# OpenthermGWMini.net
KiCad netlist of a schematic drawn in EAGLE
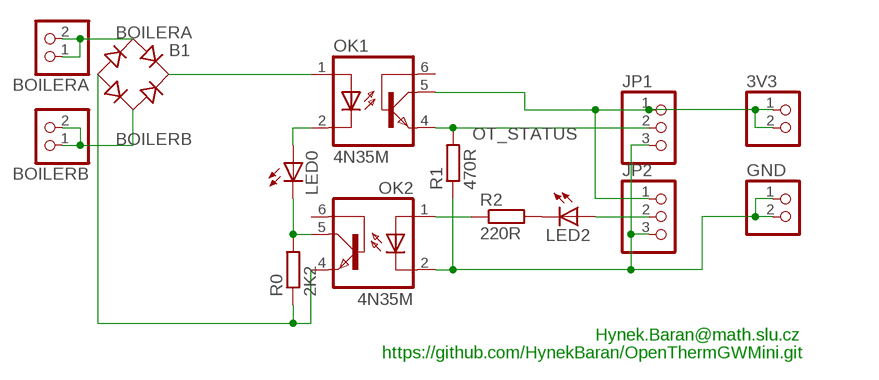
[diagram p0: schematic, sheet 1]

(export (version "E")
  (design (tool "Eeschema 10.0.6"))
  (components
    (comp (ref "3V3")
      (value "PINHD-1X2")
      (footprint "eagle-import:1X02")
      (libsource (lib "eagle-import") (part "pinheadHB_PINHD-1X2"))
    )
    (comp (ref "B1")
      (value "RB1A")
      (footprint "eagle-import:RB1A")
      (libsource (lib "eagle-import") (part "RB1A"))
    )
    (comp (ref "BOILERA")
      (value "PINHD-1X2")
      (footprint "eagle-import:1X02")
      (libsource (lib "eagle-import") (part "PINHD-1X2"))
    )
    (comp (ref "BOILERB")
      (value "PINHD-1X2")
      (footprint "eagle-import:1X02")
      (libsource (lib "eagle-import") (part "PINHD-1X2"))
    )
    (comp (ref "GND")
      (value "PINHD-1X2")
      (footprint "eagle-import:1X02")
      (libsource (lib "eagle-import") (part "pinheadHB_PINHD-1X2"))
    )
    (comp (ref "JP1")
      (value "PINHD-1X3")
      (footprint "eagle-import:1X03")
      (libsource (lib "eagle-import") (part "PINHD-1X3"))
    )
    (comp (ref "JP2")
      (value "PINHD-1X3")
      (footprint "eagle-import:1X03")
      (libsource (lib "eagle-import") (part "PINHD-1X3"))
    )
    (comp (ref "LED0")
      (value "LED3MM")
      (footprint "eagle-import:LED3MM")
      (libsource (lib "eagle-import") (part "LED3MM"))
    )
    (comp (ref "LED2")
      (value "LED3MM")
      (footprint "eagle-import:LED3MM")
      (libsource (lib "eagle-import") (part "LED3MM"))
    )
    (comp (ref "OK1")
      (value "4N35M")
      (footprint "eagle-import:DIL06")
      (fields (field (name "MPN") "4N35-M"))
      (libsource (lib "eagle-import") (part "4N?M35"))
    )
    (comp (ref "OK2")
      (value "4N35M")
      (footprint "eagle-import:DIL06")
      (fields (field (name "MPN") "4N35-M"))
      (libsource (lib "eagle-import") (part "4N?M35"))
    )
    (comp (ref "R0")
      (value "2K2")
      (footprint "eagle-import:0204_5")
      (libsource (lib "eagle-import") (part "R-EU_0204/5"))
    )
    (comp (ref "R1")
      (value "470R")
      (footprint "eagle-import:0204_5")
      (libsource (lib "eagle-import") (part "R-EU_0204/5"))
    )
    (comp (ref "R2")
      (value "220R")
      (footprint "eagle-import:0204_5")
      (libsource (lib "eagle-import") (part "R-EU_0204/5"))
    )
  )
  (nets
    (net (code "1") (name "/BOILERA") (class "Default")
      (node (ref "B1") (pin "AC1") (pinfunction "AC1_AC1") (pintype "passive"))
      (node (ref "BOILERA") (pin "1") (pinfunction "1_1") (pintype "passive"))
      (node (ref "BOILERA") (pin "2") (pinfunction "2_2") (pintype "passive"))
    )
    (net (code "2") (name "/BOILERB") (class "Default")
      (node (ref "B1") (pin "AC2") (pinfunction "AC2_AC2") (pintype "passive"))
      (node (ref "BOILERB") (pin "1") (pinfunction "1_1") (pintype "passive"))
      (node (ref "BOILERB") (pin "2") (pinfunction "2_2") (pintype "passive"))
    )
    (net (code "3") (name "/OT_STATUS") (class "Default")
      (node (ref "JP1") (pin "2") (pinfunction "2_2") (pintype "passive"))
      (node (ref "OK1") (pin "4") (pinfunction "EMI_4") (pintype "passive"))
      (node (ref "R1") (pin "2") (pinfunction "2_2") (pintype "passive"))
    )
    (net (code "4") (name "Net-(JP2-Pad2)") (class "Default")
      (node (ref "JP2") (pin "2") (pinfunction "2_2") (pintype "passive"))
      (node (ref "LED2") (pin "A") (pinfunction "A_A") (pintype "passive"))
    )
    (net (code "5") (name "Net-(LED0-C)") (class "Default")
      (node (ref "LED0") (pin "K") (pinfunction "C_K") (pintype "passive"))
      (node (ref "OK2") (pin "5") (pinfunction "COL_5") (pintype "passive"))
      (node (ref "R0") (pin "2") (pinfunction "2_2") (pintype "passive"))
    )
    (net (code "6") (name "Net-(LED2-C)") (class "Default")
      (node (ref "LED2") (pin "K") (pinfunction "C_K") (pintype "passive"))
      (node (ref "R2") (pin "2") (pinfunction "2_2") (pintype "passive"))
    )
    (net (code "7") (name "Net-(OK1-A)") (class "Default")
      (node (ref "B1") (pin "+") (pinfunction "+_+") (pintype "passive"))
      (node (ref "OK1") (pin "1") (pinfunction "A_1") (pintype "passive"))
    )
    (net (code "8") (name "Net-(OK1-C)") (class "Default")
      (node (ref "LED0") (pin "A") (pinfunction "A_A") (pintype "passive"))
      (node (ref "OK1") (pin "2") (pinfunction "C_2") (pintype "passive"))
    )
    (net (code "9") (name "Net-(OK1-COL)") (class "Default")
      (node (ref "3V3") (pin "1") (pinfunction "1_1") (pintype "passive"))
      (node (ref "3V3") (pin "2") (pinfunction "2_2") (pintype "passive"))
      (node (ref "JP1") (pin "1") (pinfunction "1_1") (pintype "passive"))
      (node (ref "JP2") (pin "1") (pinfunction "1_1") (pintype "passive"))
      (node (ref "OK1") (pin "5") (pinfunction "COL_5") (pintype "passive"))
    )
    (net (code "10") (name "Net-(OK2-A)") (class "Default")
      (node (ref "OK2") (pin "1") (pinfunction "A_1") (pintype "passive"))
      (node (ref "R2") (pin "1") (pinfunction "1_1") (pintype "passive"))
    )
    (net (code "11") (name "Net-(OK2-C)") (class "Default")
      (node (ref "GND") (pin "1") (pinfunction "1_1") (pintype "passive"))
      (node (ref "GND") (pin "2") (pinfunction "2_2") (pintype "passive"))
      (node (ref "JP1") (pin "3") (pinfunction "3_3") (pintype "passive"))
      (node (ref "JP2") (pin "3") (pinfunction "3_3") (pintype "passive"))
      (node (ref "OK2") (pin "2") (pinfunction "C_2") (pintype "passive"))
      (node (ref "R1") (pin "1") (pinfunction "1_1") (pintype "passive"))
    )
    (net (code "12") (name "Net-(OK2-EMI)") (class "Default")
      (node (ref "B1") (pin "-") (pinfunction "-_-") (pintype "passive"))
      (node (ref "OK2") (pin "4") (pinfunction "EMI_4") (pintype "passive"))
      (node (ref "R0") (pin "1") (pinfunction "1_1") (pintype "passive"))
    )
    (net (code "13") (name "unconnected-(OK1-BAS-Pad6)") (class "Default")
      (node (ref "OK1") (pin "6") (pinfunction "BAS_6") (pintype "passive"))
    )
    (net (code "14") (name "unconnected-(OK2-BAS-Pad6)") (class "Default")
      (node (ref "OK2") (pin "6") (pinfunction "BAS_6") (pintype "passive"))
    )
  )
)
